# Sheet.net
KiCad netlist of a schematic drawn in Altium Designer
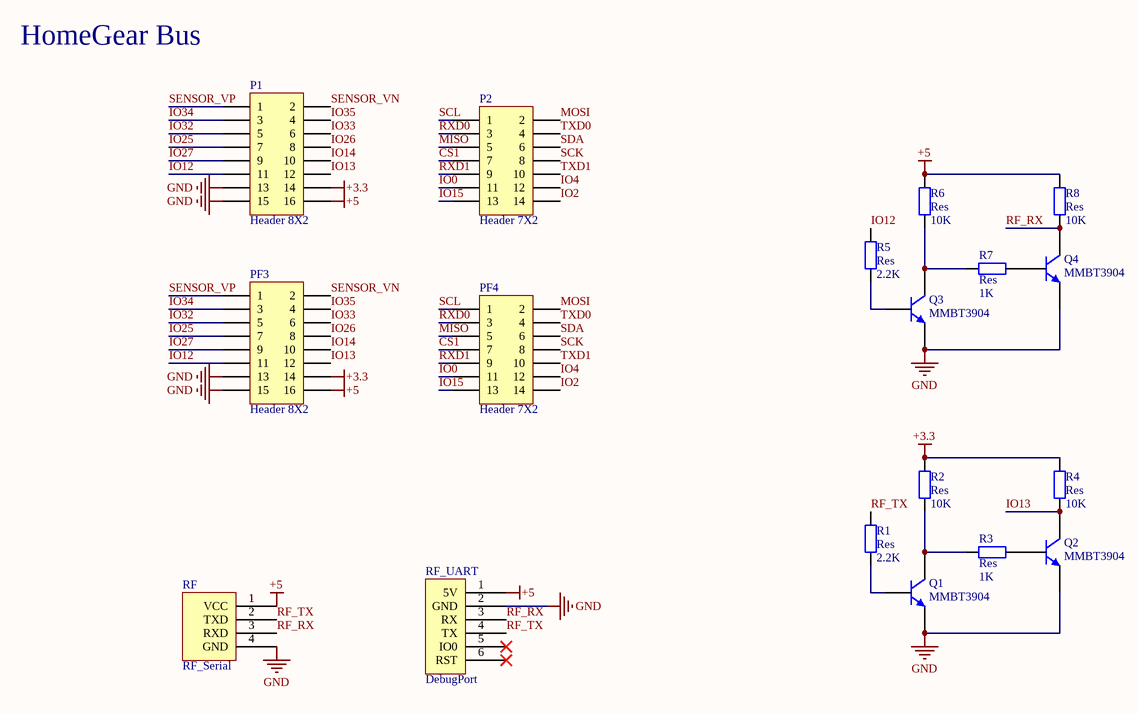
[diagram p0: Sheet.SchDoc]

(export (version "E")
  (design (tool "Eeschema 10.0.6"))
  (components
    (comp (ref "P1")
      (value "Header 8X2")
      (footprint "SMD_PIN_HDR8x2_2.0MM")
      (description "Header, 8-Pin, Dual row")
      (fields (field (name "PUBLISHER") "Altium Limited"))
      (libsource (lib "Miscellaneous Connectors") (part "Header 8X2"))
    )
    (comp (ref "P2")
      (value "Header 7X2")
      (footprint "SMD_PIN_HDR7x2_2.0MM")
      (description "Header, 7-Pin, Dual row")
      (fields (field (name "PUBLISHER") "Altium Limited"))
      (libsource (lib "Miscellaneous Connectors") (part "Header 7X2"))
    )
    (comp (ref "PF3")
      (value "Header 8X2")
      (footprint "SMD_FEM_HDR8x2_2.0MM")
      (description "Header, 8-Pin, Dual row")
      (fields (field (name "PUBLISHER") "Altium Limited"))
      (libsource (lib "Miscellaneous Connectors") (part "Header 8X2"))
    )
    (comp (ref "PF4")
      (value "Header 7X2")
      (footprint "SMD_FEM_HDR7x2_2.0MM")
      (description "Header, 7-Pin, Dual row")
      (fields (field (name "PUBLISHER") "Altium Limited"))
      (libsource (lib "Miscellaneous Connectors") (part "Header 7X2"))
    )
    (comp (ref "Q1") (value "MMBT3904") (footprint "SOT-23B_N") (libsource (lib "我的元件库") (part "MMBT3904")))
    (comp (ref "Q2") (value "MMBT3904") (footprint "SOT-23B_N") (libsource (lib "我的元件库") (part "MMBT3904")))
    (comp (ref "Q3") (value "MMBT3904") (footprint "SOT-23B_N") (libsource (lib "我的元件库") (part "MMBT3904")))
    (comp (ref "Q4") (value "MMBT3904") (footprint "SOT-23B_N") (libsource (lib "我的元件库") (part "MMBT3904")))
    (comp (ref "R1")
      (value "Res")
      (footprint "My0603")
      (description "Resistor")
      (fields (field (name "ALTIUM_VALUE") "2.2K") (field (name "PUBLISHER") "Altium Limited"))
      (libsource (lib "Miscellaneous Devices") (part "Res2"))
    )
    (comp (ref "R2")
      (value "Res")
      (footprint "My0603")
      (description "Resistor")
      (fields (field (name "ALTIUM_VALUE") "10K") (field (name "PUBLISHER") "Altium Limited"))
      (libsource (lib "Miscellaneous Devices") (part "Res2"))
    )
    (comp (ref "R3")
      (value "Res")
      (footprint "My0603")
      (description "Resistor")
      (fields (field (name "ALTIUM_VALUE") "1K") (field (name "PUBLISHER") "Altium Limited"))
      (libsource (lib "") (part "Res2_1"))
    )
    (comp (ref "R4")
      (value "Res")
      (footprint "My0603")
      (description "Resistor")
      (fields (field (name "ALTIUM_VALUE") "10K") (field (name "PUBLISHER") "Altium Limited"))
      (libsource (lib "Miscellaneous Devices") (part "Res2"))
    )
    (comp (ref "R5")
      (value "Res")
      (footprint "My0603")
      (description "Resistor")
      (fields (field (name "ALTIUM_VALUE") "2.2K") (field (name "PUBLISHER") "Altium Limited"))
      (libsource (lib "Miscellaneous Devices") (part "Res2"))
    )
    (comp (ref "R6")
      (value "Res")
      (footprint "My0603")
      (description "Resistor")
      (fields (field (name "ALTIUM_VALUE") "10K") (field (name "PUBLISHER") "Altium Limited"))
      (libsource (lib "Miscellaneous Devices") (part "Res2"))
    )
    (comp (ref "R7")
      (value "Res")
      (footprint "My0603")
      (description "Resistor")
      (fields (field (name "ALTIUM_VALUE") "1K") (field (name "PUBLISHER") "Altium Limited"))
      (libsource (lib "") (part "Res2_1"))
    )
    (comp (ref "R8")
      (value "Res")
      (footprint "My0603")
      (description "Resistor")
      (fields (field (name "ALTIUM_VALUE") "10K") (field (name "PUBLISHER") "Altium Limited"))
      (libsource (lib "Miscellaneous Devices") (part "Res2"))
    )
    (comp (ref "RF")
      (value "RF_Serial")
      (footprint "Serial_RF_Module")
      (libsource (lib "我的元件库") (part "RF_Serial"))
    )
    (comp (ref "RF_UART")
      (value "DebugPort")
      (footprint "XH2.54-WI-6P")
      (libsource (lib "ESP12_BME280_OLED_IR") (part "DebugPort"))
    )
  )
  (nets
    (net (code "1") (name "+3.3") (class "Default")
      (node (ref "P1") (pin "14") (pinfunction "14_14") (pintype "passive"))
      (node (ref "PF3") (pin "14") (pinfunction "14_14") (pintype "passive"))
      (node (ref "R2") (pin "1") (pinfunction "1_1") (pintype "passive"))
      (node (ref "R4") (pin "1") (pinfunction "1_1") (pintype "passive"))
    )
    (net (code "2") (name "+5") (class "Default")
      (node (ref "P1") (pin "16") (pinfunction "16_16") (pintype "passive"))
      (node (ref "PF3") (pin "16") (pinfunction "16_16") (pintype "passive"))
      (node (ref "R6") (pin "1") (pinfunction "1_1") (pintype "passive"))
      (node (ref "R8") (pin "1") (pinfunction "1_1") (pintype "passive"))
      (node (ref "RF") (pin "1") (pinfunction "VCC_1") (pintype "passive"))
      (node (ref "RF_UART") (pin "1") (pinfunction "5V_1") (pintype "passive"))
    )
    (net (code "3") (name "/CS1") (class "Default")
      (node (ref "P2") (pin "7") (pinfunction "7_7") (pintype "passive"))
      (node (ref "PF4") (pin "7") (pinfunction "7_7") (pintype "passive"))
    )
    (net (code "4") (name "/IO0") (class "Default")
      (node (ref "P2") (pin "11") (pinfunction "11_11") (pintype "passive"))
      (node (ref "PF4") (pin "11") (pinfunction "11_11") (pintype "passive"))
    )
    (net (code "5") (name "/IO2") (class "Default")
      (node (ref "P2") (pin "14") (pinfunction "14_14") (pintype "passive"))
      (node (ref "PF4") (pin "14") (pinfunction "14_14") (pintype "passive"))
    )
    (net (code "6") (name "/IO4") (class "Default")
      (node (ref "P2") (pin "12") (pinfunction "12_12") (pintype "passive"))
      (node (ref "PF4") (pin "12") (pinfunction "12_12") (pintype "passive"))
    )
    (net (code "7") (name "/IO12") (class "Default")
      (node (ref "P1") (pin "11") (pinfunction "11_11") (pintype "passive"))
      (node (ref "PF3") (pin "11") (pinfunction "11_11") (pintype "passive"))
      (node (ref "R5") (pin "1") (pinfunction "1_1") (pintype "passive"))
    )
    (net (code "8") (name "/IO13") (class "Default")
      (node (ref "P1") (pin "12") (pinfunction "12_12") (pintype "passive"))
      (node (ref "PF3") (pin "12") (pinfunction "12_12") (pintype "passive"))
      (node (ref "Q2") (pin "3") (pinfunction "C_3") (pintype "passive"))
      (node (ref "R4") (pin "2") (pinfunction "2_2") (pintype "passive"))
    )
    (net (code "9") (name "/IO14") (class "Default")
      (node (ref "P1") (pin "10") (pinfunction "10_10") (pintype "passive"))
      (node (ref "PF3") (pin "10") (pinfunction "10_10") (pintype "passive"))
    )
    (net (code "10") (name "/IO15") (class "Default")
      (node (ref "P2") (pin "13") (pinfunction "13_13") (pintype "passive"))
      (node (ref "PF4") (pin "13") (pinfunction "13_13") (pintype "passive"))
    )
    (net (code "11") (name "/IO25") (class "Default")
      (node (ref "P1") (pin "7") (pinfunction "7_7") (pintype "passive"))
      (node (ref "PF3") (pin "7") (pinfunction "7_7") (pintype "passive"))
    )
    (net (code "12") (name "/IO26") (class "Default")
      (node (ref "P1") (pin "8") (pinfunction "8_8") (pintype "passive"))
      (node (ref "PF3") (pin "8") (pinfunction "8_8") (pintype "passive"))
    )
    (net (code "13") (name "/IO27") (class "Default")
      (node (ref "P1") (pin "9") (pinfunction "9_9") (pintype "passive"))
      (node (ref "PF3") (pin "9") (pinfunction "9_9") (pintype "passive"))
    )
    (net (code "14") (name "/IO32") (class "Default")
      (node (ref "P1") (pin "5") (pinfunction "5_5") (pintype "passive"))
      (node (ref "PF3") (pin "5") (pinfunction "5_5") (pintype "passive"))
    )
    (net (code "15") (name "/IO33") (class "Default")
      (node (ref "P1") (pin "6") (pinfunction "6_6") (pintype "passive"))
      (node (ref "PF3") (pin "6") (pinfunction "6_6") (pintype "passive"))
    )
    (net (code "16") (name "/IO34") (class "Default")
      (node (ref "P1") (pin "3") (pinfunction "3_3") (pintype "passive"))
      (node (ref "PF3") (pin "3") (pinfunction "3_3") (pintype "passive"))
    )
    (net (code "17") (name "/IO35") (class "Default")
      (node (ref "P1") (pin "4") (pinfunction "4_4") (pintype "passive"))
      (node (ref "PF3") (pin "4") (pinfunction "4_4") (pintype "passive"))
    )
    (net (code "18") (name "/MISO") (class "Default")
      (node (ref "P2") (pin "5") (pinfunction "5_5") (pintype "passive"))
      (node (ref "PF4") (pin "5") (pinfunction "5_5") (pintype "passive"))
    )
    (net (code "19") (name "/MOSI") (class "Default")
      (node (ref "P2") (pin "2") (pinfunction "2_2") (pintype "passive"))
      (node (ref "PF4") (pin "2") (pinfunction "2_2") (pintype "passive"))
    )
    (net (code "20") (name "/RF_RX") (class "Default")
      (node (ref "Q4") (pin "3") (pinfunction "C_3") (pintype "passive"))
      (node (ref "R8") (pin "2") (pinfunction "2_2") (pintype "passive"))
      (node (ref "RF") (pin "3") (pinfunction "RXD_3") (pintype "passive"))
      (node (ref "RF_UART") (pin "3") (pinfunction "RX_3") (pintype "passive"))
    )
    (net (code "21") (name "/RF_TX") (class "Default")
      (node (ref "R1") (pin "1") (pinfunction "1_1") (pintype "passive"))
      (node (ref "RF") (pin "2") (pinfunction "TXD_2") (pintype "passive"))
      (node (ref "RF_UART") (pin "4") (pinfunction "TX_4") (pintype "passive"))
    )
    (net (code "22") (name "/RXD0") (class "Default")
      (node (ref "P2") (pin "3") (pinfunction "3_3") (pintype "passive"))
      (node (ref "PF4") (pin "3") (pinfunction "3_3") (pintype "passive"))
    )
    (net (code "23") (name "/RXD1") (class "Default")
      (node (ref "P2") (pin "9") (pinfunction "9_9") (pintype "passive"))
      (node (ref "PF4") (pin "9") (pinfunction "9_9") (pintype "passive"))
    )
    (net (code "24") (name "/SCK") (class "Default")
      (node (ref "P2") (pin "8") (pinfunction "8_8") (pintype "passive"))
      (node (ref "PF4") (pin "8") (pinfunction "8_8") (pintype "passive"))
    )
    (net (code "25") (name "/SCL") (class "Default")
      (node (ref "P2") (pin "1") (pinfunction "1_1") (pintype "passive"))
      (node (ref "PF4") (pin "1") (pinfunction "1_1") (pintype "passive"))
    )
    (net (code "26") (name "/SDA") (class "Default")
      (node (ref "P2") (pin "6") (pinfunction "6_6") (pintype "passive"))
      (node (ref "PF4") (pin "6") (pinfunction "6_6") (pintype "passive"))
    )
    (net (code "27") (name "/SENSOR_VN") (class "Default")
      (node (ref "P1") (pin "2") (pinfunction "2_2") (pintype "passive"))
      (node (ref "PF3") (pin "2") (pinfunction "2_2") (pintype "passive"))
    )
    (net (code "28") (name "/SENSOR_VP") (class "Default")
      (node (ref "P1") (pin "1") (pinfunction "1_1") (pintype "passive"))
      (node (ref "PF3") (pin "1") (pinfunction "1_1") (pintype "passive"))
    )
    (net (code "29") (name "/TXD0") (class "Default")
      (node (ref "P2") (pin "4") (pinfunction "4_4") (pintype "passive"))
      (node (ref "PF4") (pin "4") (pinfunction "4_4") (pintype "passive"))
    )
    (net (code "30") (name "/TXD1") (class "Default")
      (node (ref "P2") (pin "10") (pinfunction "10_10") (pintype "passive"))
      (node (ref "PF4") (pin "10") (pinfunction "10_10") (pintype "passive"))
    )
    (net (code "31") (name "GND") (class "Default")
      (node (ref "P1") (pin "13") (pinfunction "13_13") (pintype "passive"))
      (node (ref "P1") (pin "15") (pinfunction "15_15") (pintype "passive"))
      (node (ref "PF3") (pin "13") (pinfunction "13_13") (pintype "passive"))
      (node (ref "PF3") (pin "15") (pinfunction "15_15") (pintype "passive"))
      (node (ref "Q1") (pin "2") (pinfunction "E_2") (pintype "passive"))
      (node (ref "Q2") (pin "2") (pinfunction "E_2") (pintype "passive"))
      (node (ref "Q3") (pin "2") (pinfunction "E_2") (pintype "passive"))
      (node (ref "Q4") (pin "2") (pinfunction "E_2") (pintype "passive"))
      (node (ref "RF") (pin "4") (pinfunction "GND_4") (pintype "passive"))
      (node (ref "RF_UART") (pin "2") (pinfunction "GND_2") (pintype "passive"))
    )
    (net (code "32") (name "Net-(Q1-B)") (class "Default")
      (node (ref "Q1") (pin "1") (pinfunction "B_1") (pintype "passive"))
      (node (ref "R1") (pin "2") (pinfunction "2_2") (pintype "passive"))
    )
    (net (code "33") (name "Net-(Q1-C)") (class "Default")
      (node (ref "Q1") (pin "3") (pinfunction "C_3") (pintype "passive"))
      (node (ref "R2") (pin "2") (pinfunction "2_2") (pintype "passive"))
      (node (ref "R3") (pin "2") (pinfunction "2_2") (pintype "passive"))
    )
    (net (code "34") (name "Net-(Q2-B)") (class "Default")
      (node (ref "Q2") (pin "1") (pinfunction "B_1") (pintype "passive"))
      (node (ref "R3") (pin "1") (pinfunction "1_1") (pintype "passive"))
    )
    (net (code "35") (name "Net-(Q3-B)") (class "Default")
      (node (ref "Q3") (pin "1") (pinfunction "B_1") (pintype "passive"))
      (node (ref "R5") (pin "2") (pinfunction "2_2") (pintype "passive"))
    )
    (net (code "36") (name "Net-(Q3-C)") (class "Default")
      (node (ref "Q3") (pin "3") (pinfunction "C_3") (pintype "passive"))
      (node (ref "R6") (pin "2") (pinfunction "2_2") (pintype "passive"))
      (node (ref "R7") (pin "2") (pinfunction "2_2") (pintype "passive"))
    )
    (net (code "37") (name "Net-(Q4-B)") (class "Default")
      (node (ref "Q4") (pin "1") (pinfunction "B_1") (pintype "passive"))
      (node (ref "R7") (pin "1") (pinfunction "1_1") (pintype "passive"))
    )
    (net (code "38") (name "unconnected-(RF_UART-IO0-Pad5)") (class "Default")
      (node (ref "RF_UART") (pin "5") (pinfunction "IO0_5") (pintype "passive+no_connect"))
    )
    (net (code "39") (name "unconnected-(RF_UART-RST-Pad6)") (class "Default")
      (node (ref "RF_UART") (pin "6") (pinfunction "RST_6") (pintype "passive+no_connect"))
    )
  )
)
